# leddriver_1.net
KiCad netlist of a schematic drawn in EAGLE
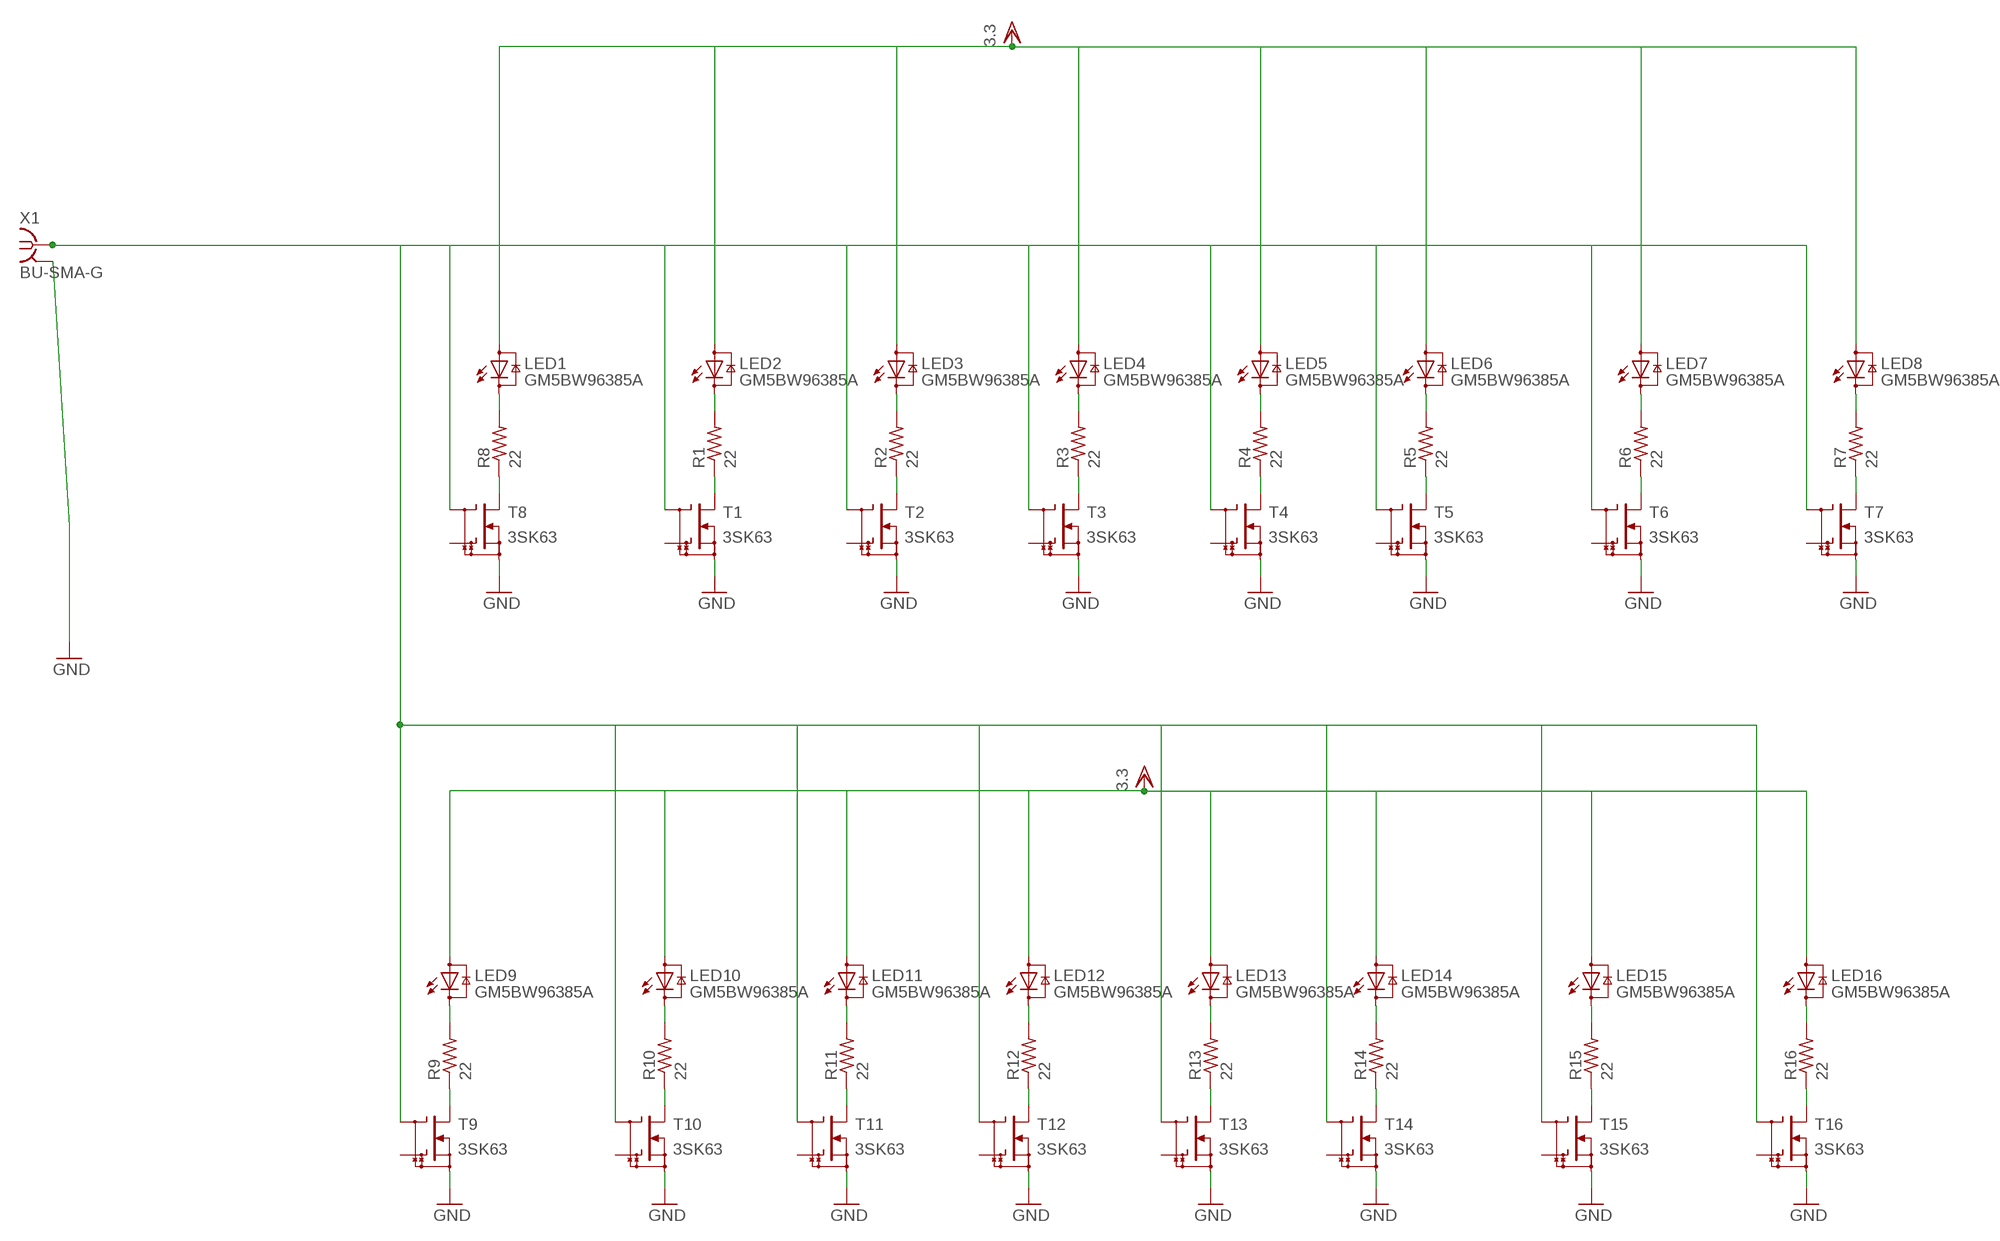
[diagram p0: schematic, sheet 1]

(export (version "E")
  (design (tool "Eeschema 10.0.6"))
  (components
    (comp (ref "LED1")
      (value "GM5BW96385A")
      (footprint "eagle-import:GM5BW96385A")
      (libsource (lib "eagle-import") (part "GM5BW96385A"))
    )
    (comp (ref "LED2")
      (value "GM5BW96385A")
      (footprint "eagle-import:GM5BW96385A")
      (libsource (lib "eagle-import") (part "GM5BW96385A"))
    )
    (comp (ref "LED3")
      (value "GM5BW96385A")
      (footprint "eagle-import:GM5BW96385A")
      (libsource (lib "eagle-import") (part "GM5BW96385A"))
    )
    (comp (ref "LED4")
      (value "GM5BW96385A")
      (footprint "eagle-import:GM5BW96385A")
      (libsource (lib "eagle-import") (part "GM5BW96385A"))
    )
    (comp (ref "LED5")
      (value "GM5BW96385A")
      (footprint "eagle-import:GM5BW96385A")
      (libsource (lib "eagle-import") (part "GM5BW96385A"))
    )
    (comp (ref "LED6")
      (value "GM5BW96385A")
      (footprint "eagle-import:GM5BW96385A")
      (libsource (lib "eagle-import") (part "GM5BW96385A"))
    )
    (comp (ref "LED7")
      (value "GM5BW96385A")
      (footprint "eagle-import:GM5BW96385A")
      (libsource (lib "eagle-import") (part "GM5BW96385A"))
    )
    (comp (ref "LED8")
      (value "GM5BW96385A")
      (footprint "eagle-import:GM5BW96385A")
      (libsource (lib "eagle-import") (part "GM5BW96385A"))
    )
    (comp (ref "LED9")
      (value "GM5BW96385A")
      (footprint "eagle-import:GM5BW96385A")
      (libsource (lib "eagle-import") (part "GM5BW96385A"))
    )
    (comp (ref "LED10")
      (value "GM5BW96385A")
      (footprint "eagle-import:GM5BW96385A")
      (libsource (lib "eagle-import") (part "GM5BW96385A"))
    )
    (comp (ref "LED11")
      (value "GM5BW96385A")
      (footprint "eagle-import:GM5BW96385A")
      (libsource (lib "eagle-import") (part "GM5BW96385A"))
    )
    (comp (ref "LED12")
      (value "GM5BW96385A")
      (footprint "eagle-import:GM5BW96385A")
      (libsource (lib "eagle-import") (part "GM5BW96385A"))
    )
    (comp (ref "LED13")
      (value "GM5BW96385A")
      (footprint "eagle-import:GM5BW96385A")
      (libsource (lib "eagle-import") (part "GM5BW96385A"))
    )
    (comp (ref "LED14")
      (value "GM5BW96385A")
      (footprint "eagle-import:GM5BW96385A")
      (libsource (lib "eagle-import") (part "GM5BW96385A"))
    )
    (comp (ref "LED15")
      (value "GM5BW96385A")
      (footprint "eagle-import:GM5BW96385A")
      (libsource (lib "eagle-import") (part "GM5BW96385A"))
    )
    (comp (ref "LED16")
      (value "GM5BW96385A")
      (footprint "eagle-import:GM5BW96385A")
      (libsource (lib "eagle-import") (part "GM5BW96385A"))
    )
    (comp (ref "R1")
      (value "22")
      (footprint "eagle-import:0207_5V")
      (libsource (lib "eagle-import") (part "R-US_0207/5V"))
    )
    (comp (ref "R2")
      (value "22")
      (footprint "eagle-import:0207_5V")
      (libsource (lib "eagle-import") (part "R-US_0207/5V"))
    )
    (comp (ref "R3")
      (value "22")
      (footprint "eagle-import:0207_5V")
      (libsource (lib "eagle-import") (part "R-US_0207/5V"))
    )
    (comp (ref "R4")
      (value "22")
      (footprint "eagle-import:0207_5V")
      (libsource (lib "eagle-import") (part "R-US_0207/5V"))
    )
    (comp (ref "R5")
      (value "22")
      (footprint "eagle-import:0207_5V")
      (libsource (lib "eagle-import") (part "R-US_0207/5V"))
    )
    (comp (ref "R6")
      (value "22")
      (footprint "eagle-import:0207_5V")
      (libsource (lib "eagle-import") (part "R-US_0207/5V"))
    )
    (comp (ref "R7")
      (value "22")
      (footprint "eagle-import:0207_5V")
      (libsource (lib "eagle-import") (part "R-US_0207/5V"))
    )
    (comp (ref "R8")
      (value "22")
      (footprint "eagle-import:0207_5V")
      (libsource (lib "eagle-import") (part "R-US_0207/5V"))
    )
    (comp (ref "R9")
      (value "22")
      (footprint "eagle-import:0207_5V")
      (libsource (lib "eagle-import") (part "R-US_0207/5V"))
    )
    (comp (ref "R10")
      (value "22")
      (footprint "eagle-import:0207_5V")
      (libsource (lib "eagle-import") (part "R-US_0207/5V"))
    )
    (comp (ref "R11")
      (value "22")
      (footprint "eagle-import:0207_5V")
      (libsource (lib "eagle-import") (part "R-US_0207/5V"))
    )
    (comp (ref "R12")
      (value "22")
      (footprint "eagle-import:0207_5V")
      (libsource (lib "eagle-import") (part "R-US_0207/5V"))
    )
    (comp (ref "R13")
      (value "22")
      (footprint "eagle-import:0207_5V")
      (libsource (lib "eagle-import") (part "R-US_0207/5V"))
    )
    (comp (ref "R14")
      (value "22")
      (footprint "eagle-import:0207_5V")
      (libsource (lib "eagle-import") (part "R-US_0207/5V"))
    )
    (comp (ref "R15")
      (value "22")
      (footprint "eagle-import:0207_5V")
      (libsource (lib "eagle-import") (part "R-US_0207/5V"))
    )
    (comp (ref "R16")
      (value "22")
      (footprint "eagle-import:0207_5V")
      (libsource (lib "eagle-import") (part "R-US_0207/5V"))
    )
    (comp (ref "T1")
      (value "3SK63")
      (footprint "eagle-import:TO72")
      (libsource (lib "eagle-import") (part "3SK63"))
    )
    (comp (ref "T2")
      (value "3SK63")
      (footprint "eagle-import:TO72")
      (libsource (lib "eagle-import") (part "3SK63"))
    )
    (comp (ref "T3")
      (value "3SK63")
      (footprint "eagle-import:TO72")
      (libsource (lib "eagle-import") (part "3SK63"))
    )
    (comp (ref "T4")
      (value "3SK63")
      (footprint "eagle-import:TO72")
      (libsource (lib "eagle-import") (part "3SK63"))
    )
    (comp (ref "T5")
      (value "3SK63")
      (footprint "eagle-import:TO72")
      (libsource (lib "eagle-import") (part "3SK63"))
    )
    (comp (ref "T6")
      (value "3SK63")
      (footprint "eagle-import:TO72")
      (libsource (lib "eagle-import") (part "3SK63"))
    )
    (comp (ref "T7")
      (value "3SK63")
      (footprint "eagle-import:TO72")
      (libsource (lib "eagle-import") (part "3SK63"))
    )
    (comp (ref "T8")
      (value "3SK63")
      (footprint "eagle-import:TO72")
      (libsource (lib "eagle-import") (part "3SK63"))
    )
    (comp (ref "T9")
      (value "3SK63")
      (footprint "eagle-import:TO72")
      (libsource (lib "eagle-import") (part "3SK63"))
    )
    (comp (ref "T10")
      (value "3SK63")
      (footprint "eagle-import:TO72")
      (libsource (lib "eagle-import") (part "3SK63"))
    )
    (comp (ref "T11")
      (value "3SK63")
      (footprint "eagle-import:TO72")
      (libsource (lib "eagle-import") (part "3SK63"))
    )
    (comp (ref "T12")
      (value "3SK63")
      (footprint "eagle-import:TO72")
      (libsource (lib "eagle-import") (part "3SK63"))
    )
    (comp (ref "T13")
      (value "3SK63")
      (footprint "eagle-import:TO72")
      (libsource (lib "eagle-import") (part "3SK63"))
    )
    (comp (ref "T14")
      (value "3SK63")
      (footprint "eagle-import:TO72")
      (libsource (lib "eagle-import") (part "3SK63"))
    )
    (comp (ref "T15")
      (value "3SK63")
      (footprint "eagle-import:TO72")
      (libsource (lib "eagle-import") (part "3SK63"))
    )
    (comp (ref "T16")
      (value "3SK63")
      (footprint "eagle-import:TO72")
      (libsource (lib "eagle-import") (part "3SK63"))
    )
    (comp (ref "X1")
      (value "BU-SMA-G")
      (footprint "eagle-import:BU-SMA-G")
      (libsource (lib "eagle-import") (part "BU-SMA-G"))
    )
  )
  (nets
    (net (code "1") (name "3.3") (class "Default")
      (node (ref "LED1") (pin "A") (pinfunction "A_A") (pintype "passive"))
      (node (ref "LED10") (pin "A") (pinfunction "A_A") (pintype "passive"))
      (node (ref "LED11") (pin "A") (pinfunction "A_A") (pintype "passive"))
      (node (ref "LED12") (pin "A") (pinfunction "A_A") (pintype "passive"))
      (node (ref "LED13") (pin "A") (pinfunction "A_A") (pintype "passive"))
      (node (ref "LED14") (pin "A") (pinfunction "A_A") (pintype "passive"))
      (node (ref "LED15") (pin "A") (pinfunction "A_A") (pintype "passive"))
      (node (ref "LED16") (pin "A") (pinfunction "A_A") (pintype "passive"))
      (node (ref "LED2") (pin "A") (pinfunction "A_A") (pintype "passive"))
      (node (ref "LED3") (pin "A") (pinfunction "A_A") (pintype "passive"))
      (node (ref "LED4") (pin "A") (pinfunction "A_A") (pintype "passive"))
      (node (ref "LED5") (pin "A") (pinfunction "A_A") (pintype "passive"))
      (node (ref "LED6") (pin "A") (pinfunction "A_A") (pintype "passive"))
      (node (ref "LED7") (pin "A") (pinfunction "A_A") (pintype "passive"))
      (node (ref "LED8") (pin "A") (pinfunction "A_A") (pintype "passive"))
      (node (ref "LED9") (pin "A") (pinfunction "A_A") (pintype "passive"))
    )
    (net (code "2") (name "GND") (class "Default")
      (node (ref "T1") (pin "4") (pinfunction "SOURCE_4") (pintype "passive"))
      (node (ref "T10") (pin "4") (pinfunction "SOURCE_4") (pintype "passive"))
      (node (ref "T11") (pin "4") (pinfunction "SOURCE_4") (pintype "passive"))
      (node (ref "T12") (pin "4") (pinfunction "SOURCE_4") (pintype "passive"))
      (node (ref "T13") (pin "4") (pinfunction "SOURCE_4") (pintype "passive"))
      (node (ref "T14") (pin "4") (pinfunction "SOURCE_4") (pintype "passive"))
      (node (ref "T15") (pin "4") (pinfunction "SOURCE_4") (pintype "passive"))
      (node (ref "T16") (pin "4") (pinfunction "SOURCE_4") (pintype "passive"))
      (node (ref "T2") (pin "4") (pinfunction "SOURCE_4") (pintype "passive"))
      (node (ref "T3") (pin "4") (pinfunction "SOURCE_4") (pintype "passive"))
      (node (ref "T4") (pin "4") (pinfunction "SOURCE_4") (pintype "passive"))
      (node (ref "T5") (pin "4") (pinfunction "SOURCE_4") (pintype "passive"))
      (node (ref "T6") (pin "4") (pinfunction "SOURCE_4") (pintype "passive"))
      (node (ref "T7") (pin "4") (pinfunction "SOURCE_4") (pintype "passive"))
      (node (ref "T8") (pin "4") (pinfunction "SOURCE_4") (pintype "passive"))
      (node (ref "T9") (pin "4") (pinfunction "SOURCE_4") (pintype "passive"))
      (node (ref "X1") (pin "2") (pinfunction "2_2") (pintype "passive"))
      (node (ref "X1") (pin "3") (pinfunction "2_3") (pintype "passive"))
      (node (ref "X1") (pin "4") (pinfunction "2_4") (pintype "passive"))
      (node (ref "X1") (pin "5") (pinfunction "2_5") (pintype "passive"))
    )
    (net (code "3") (name "Net-(LED1-PadC)") (class "Default")
      (node (ref "LED1") (pin "C") (pinfunction "C_C") (pintype "passive"))
      (node (ref "R8") (pin "2") (pinfunction "2_2") (pintype "passive"))
    )
    (net (code "4") (name "Net-(LED2-PadC)") (class "Default")
      (node (ref "LED2") (pin "C") (pinfunction "C_C") (pintype "passive"))
      (node (ref "R1") (pin "2") (pinfunction "2_2") (pintype "passive"))
    )
    (net (code "5") (name "Net-(LED3-PadC)") (class "Default")
      (node (ref "LED3") (pin "C") (pinfunction "C_C") (pintype "passive"))
      (node (ref "R2") (pin "2") (pinfunction "2_2") (pintype "passive"))
    )
    (net (code "6") (name "Net-(LED4-PadC)") (class "Default")
      (node (ref "LED4") (pin "C") (pinfunction "C_C") (pintype "passive"))
      (node (ref "R3") (pin "2") (pinfunction "2_2") (pintype "passive"))
    )
    (net (code "7") (name "Net-(LED5-PadC)") (class "Default")
      (node (ref "LED5") (pin "C") (pinfunction "C_C") (pintype "passive"))
      (node (ref "R4") (pin "2") (pinfunction "2_2") (pintype "passive"))
    )
    (net (code "8") (name "Net-(LED6-PadC)") (class "Default")
      (node (ref "LED6") (pin "C") (pinfunction "C_C") (pintype "passive"))
      (node (ref "R5") (pin "2") (pinfunction "2_2") (pintype "passive"))
    )
    (net (code "9") (name "Net-(LED7-PadC)") (class "Default")
      (node (ref "LED7") (pin "C") (pinfunction "C_C") (pintype "passive"))
      (node (ref "R6") (pin "2") (pinfunction "2_2") (pintype "passive"))
    )
    (net (code "10") (name "Net-(LED8-PadC)") (class "Default")
      (node (ref "LED8") (pin "C") (pinfunction "C_C") (pintype "passive"))
      (node (ref "R7") (pin "2") (pinfunction "2_2") (pintype "passive"))
    )
    (net (code "11") (name "Net-(LED9-PadC)") (class "Default")
      (node (ref "LED9") (pin "C") (pinfunction "C_C") (pintype "passive"))
      (node (ref "R9") (pin "2") (pinfunction "2_2") (pintype "passive"))
    )
    (net (code "12") (name "Net-(LED10-PadC)") (class "Default")
      (node (ref "LED10") (pin "C") (pinfunction "C_C") (pintype "passive"))
      (node (ref "R10") (pin "2") (pinfunction "2_2") (pintype "passive"))
    )
    (net (code "13") (name "Net-(LED11-PadC)") (class "Default")
      (node (ref "LED11") (pin "C") (pinfunction "C_C") (pintype "passive"))
      (node (ref "R11") (pin "2") (pinfunction "2_2") (pintype "passive"))
    )
    (net (code "14") (name "Net-(LED12-PadC)") (class "Default")
      (node (ref "LED12") (pin "C") (pinfunction "C_C") (pintype "passive"))
      (node (ref "R12") (pin "2") (pinfunction "2_2") (pintype "passive"))
    )
    (net (code "15") (name "Net-(LED13-PadC)") (class "Default")
      (node (ref "LED13") (pin "C") (pinfunction "C_C") (pintype "passive"))
      (node (ref "R13") (pin "2") (pinfunction "2_2") (pintype "passive"))
    )
    (net (code "16") (name "Net-(LED14-PadC)") (class "Default")
      (node (ref "LED14") (pin "C") (pinfunction "C_C") (pintype "passive"))
      (node (ref "R14") (pin "2") (pinfunction "2_2") (pintype "passive"))
    )
    (net (code "17") (name "Net-(LED15-PadC)") (class "Default")
      (node (ref "LED15") (pin "C") (pinfunction "C_C") (pintype "passive"))
      (node (ref "R15") (pin "2") (pinfunction "2_2") (pintype "passive"))
    )
    (net (code "18") (name "Net-(LED16-PadC)") (class "Default")
      (node (ref "LED16") (pin "C") (pinfunction "C_C") (pintype "passive"))
      (node (ref "R16") (pin "2") (pinfunction "2_2") (pintype "passive"))
    )
    (net (code "19") (name "Net-(T1-DRAIN)") (class "Default")
      (node (ref "R1") (pin "1") (pinfunction "1_1") (pintype "passive"))
      (node (ref "T1") (pin "1") (pinfunction "DRAIN_1") (pintype "passive"))
    )
    (net (code "20") (name "Net-(T1-G1)") (class "Default")
      (node (ref "T1") (pin "3") (pinfunction "G1_3") (pintype "passive"))
      (node (ref "T10") (pin "3") (pinfunction "G1_3") (pintype "passive"))
      (node (ref "T11") (pin "3") (pinfunction "G1_3") (pintype "passive"))
      (node (ref "T12") (pin "3") (pinfunction "G1_3") (pintype "passive"))
      (node (ref "T13") (pin "3") (pinfunction "G1_3") (pintype "passive"))
      (node (ref "T14") (pin "3") (pinfunction "G1_3") (pintype "passive"))
      (node (ref "T15") (pin "3") (pinfunction "G1_3") (pintype "passive"))
      (node (ref "T16") (pin "3") (pinfunction "G1_3") (pintype "passive"))
      (node (ref "T2") (pin "3") (pinfunction "G1_3") (pintype "passive"))
      (node (ref "T3") (pin "3") (pinfunction "G1_3") (pintype "passive"))
      (node (ref "T4") (pin "3") (pinfunction "G1_3") (pintype "passive"))
      (node (ref "T5") (pin "3") (pinfunction "G1_3") (pintype "passive"))
      (node (ref "T6") (pin "3") (pinfunction "G1_3") (pintype "passive"))
      (node (ref "T7") (pin "3") (pinfunction "G1_3") (pintype "passive"))
      (node (ref "T8") (pin "3") (pinfunction "G1_3") (pintype "passive"))
      (node (ref "T9") (pin "3") (pinfunction "G1_3") (pintype "passive"))
      (node (ref "X1") (pin "1") (pinfunction "1_1") (pintype "passive"))
    )
    (net (code "21") (name "Net-(T2-DRAIN)") (class "Default")
      (node (ref "R2") (pin "1") (pinfunction "1_1") (pintype "passive"))
      (node (ref "T2") (pin "1") (pinfunction "DRAIN_1") (pintype "passive"))
    )
    (net (code "22") (name "Net-(T3-DRAIN)") (class "Default")
      (node (ref "R3") (pin "1") (pinfunction "1_1") (pintype "passive"))
      (node (ref "T3") (pin "1") (pinfunction "DRAIN_1") (pintype "passive"))
    )
    (net (code "23") (name "Net-(T4-DRAIN)") (class "Default")
      (node (ref "R4") (pin "1") (pinfunction "1_1") (pintype "passive"))
      (node (ref "T4") (pin "1") (pinfunction "DRAIN_1") (pintype "passive"))
    )
    (net (code "24") (name "Net-(T5-DRAIN)") (class "Default")
      (node (ref "R5") (pin "1") (pinfunction "1_1") (pintype "passive"))
      (node (ref "T5") (pin "1") (pinfunction "DRAIN_1") (pintype "passive"))
    )
    (net (code "25") (name "Net-(T6-DRAIN)") (class "Default")
      (node (ref "R6") (pin "1") (pinfunction "1_1") (pintype "passive"))
      (node (ref "T6") (pin "1") (pinfunction "DRAIN_1") (pintype "passive"))
    )
    (net (code "26") (name "Net-(T7-DRAIN)") (class "Default")
      (node (ref "R7") (pin "1") (pinfunction "1_1") (pintype "passive"))
      (node (ref "T7") (pin "1") (pinfunction "DRAIN_1") (pintype "passive"))
    )
    (net (code "27") (name "Net-(T8-DRAIN)") (class "Default")
      (node (ref "R8") (pin "1") (pinfunction "1_1") (pintype "passive"))
      (node (ref "T8") (pin "1") (pinfunction "DRAIN_1") (pintype "passive"))
    )
    (net (code "28") (name "Net-(T9-DRAIN)") (class "Default")
      (node (ref "R9") (pin "1") (pinfunction "1_1") (pintype "passive"))
      (node (ref "T9") (pin "1") (pinfunction "DRAIN_1") (pintype "passive"))
    )
    (net (code "29") (name "Net-(T10-DRAIN)") (class "Default")
      (node (ref "R10") (pin "1") (pinfunction "1_1") (pintype "passive"))
      (node (ref "T10") (pin "1") (pinfunction "DRAIN_1") (pintype "passive"))
    )
    (net (code "30") (name "Net-(T11-DRAIN)") (class "Default")
      (node (ref "R11") (pin "1") (pinfunction "1_1") (pintype "passive"))
      (node (ref "T11") (pin "1") (pinfunction "DRAIN_1") (pintype "passive"))
    )
    (net (code "31") (name "Net-(T12-DRAIN)") (class "Default")
      (node (ref "R12") (pin "1") (pinfunction "1_1") (pintype "passive"))
      (node (ref "T12") (pin "1") (pinfunction "DRAIN_1") (pintype "passive"))
    )
    (net (code "32") (name "Net-(T13-DRAIN)") (class "Default")
      (node (ref "R13") (pin "1") (pinfunction "1_1") (pintype "passive"))
      (node (ref "T13") (pin "1") (pinfunction "DRAIN_1") (pintype "passive"))
    )
    (net (code "33") (name "Net-(T14-DRAIN)") (class "Default")
      (node (ref "R14") (pin "1") (pinfunction "1_1") (pintype "passive"))
      (node (ref "T14") (pin "1") (pinfunction "DRAIN_1") (pintype "passive"))
    )
    (net (code "34") (name "Net-(T15-DRAIN)") (class "Default")
      (node (ref "R15") (pin "1") (pinfunction "1_1") (pintype "passive"))
      (node (ref "T15") (pin "1") (pinfunction "DRAIN_1") (pintype "passive"))
    )
    (net (code "35") (name "Net-(T16-DRAIN)") (class "Default")
      (node (ref "R16") (pin "1") (pinfunction "1_1") (pintype "passive"))
      (node (ref "T16") (pin "1") (pinfunction "DRAIN_1") (pintype "passive"))
    )
    (net (code "36") (name "unconnected-(T1-G2-Pad2)") (class "Default")
      (node (ref "T1") (pin "2") (pinfunction "G2_2") (pintype "passive"))
    )
    (net (code "37") (name "unconnected-(T2-G2-Pad2)") (class "Default")
      (node (ref "T2") (pin "2") (pinfunction "G2_2") (pintype "passive"))
    )
    (net (code "38") (name "unconnected-(T3-G2-Pad2)") (class "Default")
      (node (ref "T3") (pin "2") (pinfunction "G2_2") (pintype "passive"))
    )
    (net (code "39") (name "unconnected-(T4-G2-Pad2)") (class "Default")
      (node (ref "T4") (pin "2") (pinfunction "G2_2") (pintype "passive"))
    )
    (net (code "40") (name "unconnected-(T5-G2-Pad2)") (class "Default")
      (node (ref "T5") (pin "2") (pinfunction "G2_2") (pintype "passive"))
    )
    (net (code "41") (name "unconnected-(T6-G2-Pad2)") (class "Default")
      (node (ref "T6") (pin "2") (pinfunction "G2_2") (pintype "passive"))
    )
    (net (code "42") (name "unconnected-(T7-G2-Pad2)") (class "Default")
      (node (ref "T7") (pin "2") (pinfunction "G2_2") (pintype "passive"))
    )
    (net (code "43") (name "unconnected-(T8-G2-Pad2)") (class "Default")
      (node (ref "T8") (pin "2") (pinfunction "G2_2") (pintype "passive"))
    )
    (net (code "44") (name "unconnected-(T9-G2-Pad2)") (class "Default")
      (node (ref "T9") (pin "2") (pinfunction "G2_2") (pintype "passive"))
    )
    (net (code "45") (name "unconnected-(T10-G2-Pad2)") (class "Default")
      (node (ref "T10") (pin "2") (pinfunction "G2_2") (pintype "passive"))
    )
    (net (code "46") (name "unconnected-(T11-G2-Pad2)") (class "Default")
      (node (ref "T11") (pin "2") (pinfunction "G2_2") (pintype "passive"))
    )
    (net (code "47") (name "unconnected-(T12-G2-Pad2)") (class "Default")
      (node (ref "T12") (pin "2") (pinfunction "G2_2") (pintype "passive"))
    )
    (net (code "48") (name "unconnected-(T13-G2-Pad2)") (class "Default")
      (node (ref "T13") (pin "2") (pinfunction "G2_2") (pintype "passive"))
    )
    (net (code "49") (name "unconnected-(T14-G2-Pad2)") (class "Default")
      (node (ref "T14") (pin "2") (pinfunction "G2_2") (pintype "passive"))
    )
    (net (code "50") (name "unconnected-(T15-G2-Pad2)") (class "Default")
      (node (ref "T15") (pin "2") (pinfunction "G2_2") (pintype "passive"))
    )
    (net (code "51") (name "unconnected-(T16-G2-Pad2)") (class "Default")
      (node (ref "T16") (pin "2") (pinfunction "G2_2") (pintype "passive"))
    )
  )
)
